# Power.net
KiCad netlist of a schematic drawn in Altium Designer
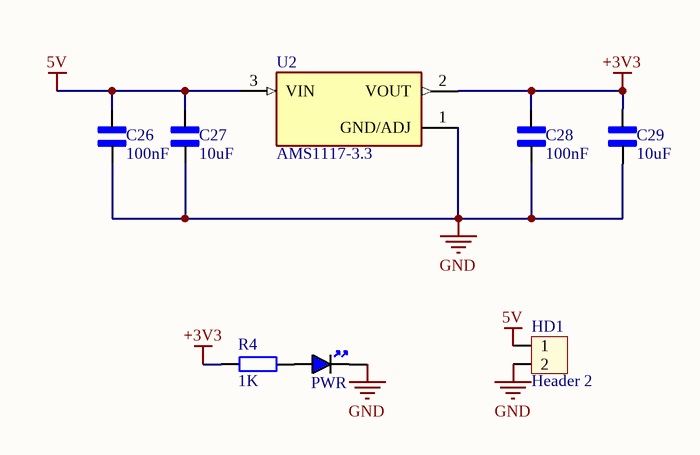
[diagram p0: Power.SchDoc]

(export (version "E")
  (design (tool "Eeschema 10.0.6"))
  (components
    (comp (ref "C26")
      (value "100nF")
      (footprint "CAPC2012X145N")
      (description "39 pF Â±2% 200V Ceramic Capacitor C0G, NP0 0805 (2012 Metric)")
      (fields (field (name "MF") "Vishay Vitramon") (field (name "MP") "VJ0805A390GXCAP"))
      (libsource (lib "VJ0805A390GXCAP") (part "VJ0805A390GXCAP"))
    )
    (comp (ref "C27")
      (value "10uF")
      (footprint "CAPC2012X145N")
      (description "39 pF Â±2% 200V Ceramic Capacitor C0G, NP0 0805 (2012 Metric)")
      (fields (field (name "MF") "Vishay Vitramon") (field (name "MP") "VJ0805A390GXCAP"))
      (libsource (lib "VJ0805A390GXCAP") (part "VJ0805A390GXCAP"))
    )
    (comp (ref "C28")
      (value "100nF")
      (footprint "CAPC2012X145N")
      (description "39 pF Â±2% 200V Ceramic Capacitor C0G, NP0 0805 (2012 Metric)")
      (fields (field (name "MF") "Vishay Vitramon") (field (name "MP") "VJ0805A390GXCAP"))
      (libsource (lib "VJ0805A390GXCAP") (part "VJ0805A390GXCAP"))
    )
    (comp (ref "C29")
      (value "10uF")
      (footprint "CAPC2012X145N")
      (description "39 pF Â±2% 200V Ceramic Capacitor C0G, NP0 0805 (2012 Metric)")
      (fields (field (name "MF") "Vishay Vitramon") (field (name "MP") "VJ0805A390GXCAP"))
      (libsource (lib "VJ0805A390GXCAP") (part "VJ0805A390GXCAP"))
    )
    (comp (ref "HD1")
      (value "Header 2")
      (footprint "HED2")
      (description "Header 2 (Green)")
      (libsource (lib "My Library") (part "Hed2"))
    )
    (comp (ref "PWR")
      (value "BLUE")
      (footprint "LED_0805_BLUE")
      (description "LED 0805 BLUE SMD")
      (libsource (lib "Schematic-Lib-PhilsLab") (part "LED_0805_BLUE"))
    )
    (comp (ref "R4")
      (value "1K")
      (footprint "SM-0805")
      (description "Resistor SMD")
      (libsource (lib "My Library") (part "RM"))
    )
    (comp (ref "U2")
      (value "AMS1117-3.3")
      (footprint "SOT229P700X180-4N")
      (description "Sot223/Pkg 1-Amp 3.3-Volt Low Drop Out Voltage Regulatator")
      (fields (field (name "MF") "Advanced Monolithic Systems"))
      (libsource (lib "My Library") (part "AMS1117-3.3"))
    )
  )
  (nets
    (net (code "1") (name "+3V3") (class "Default")
      (node (ref "C28") (pin "2") (pinfunction "2_2") (pintype "passive"))
      (node (ref "C29") (pin "2") (pinfunction "2_2") (pintype "passive"))
      (node (ref "R4") (pin "1") (pinfunction "1_1") (pintype "passive"))
      (node (ref "U2") (pin "2") (pinfunction "VOUT_2") (pintype "output"))
    )
    (net (code "2") (name "5V") (class "Default")
      (node (ref "C26") (pin "2") (pinfunction "2_2") (pintype "passive"))
      (node (ref "C27") (pin "2") (pinfunction "2_2") (pintype "passive"))
      (node (ref "HD1") (pin "1") (pinfunction "1_1") (pintype "passive"))
      (node (ref "U2") (pin "3") (pinfunction "VIN_3") (pintype "input"))
    )
    (net (code "3") (name "GND") (class "Default")
      (node (ref "C26") (pin "1") (pinfunction "1_1") (pintype "passive"))
      (node (ref "C27") (pin "1") (pinfunction "1_1") (pintype "passive"))
      (node (ref "C28") (pin "1") (pinfunction "1_1") (pintype "passive"))
      (node (ref "C29") (pin "1") (pinfunction "1_1") (pintype "passive"))
      (node (ref "HD1") (pin "2") (pinfunction "2_2") (pintype "passive"))
      (node (ref "PWR") (pin "K") (pinfunction "K_K") (pintype "passive"))
      (node (ref "U2") (pin "1") (pinfunction "GND/ADJ_1") (pintype "power_in"))
    )
    (net (code "4") (name "Net-(PWR-PadA)") (class "Default")
      (node (ref "PWR") (pin "A") (pinfunction "A_A") (pintype "passive"))
      (node (ref "R4") (pin "2") (pinfunction "2_2") (pintype "passive"))
    )
  )
)
